# Twintig-FCC-Metacarpal.net
KiCad netlist of a schematic drawn in Altium Designer
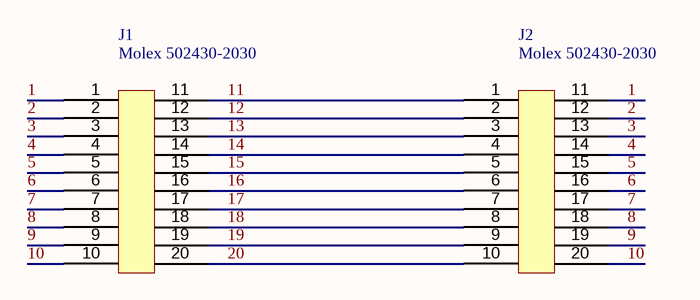
[diagram p0: Twintig-FCC-Metacarpal.SchDoc]

(export (version "E")
  (design (tool "Eeschema 10.0.6"))
  (components
    (comp (ref "J1")
      (value "Molex 502430-2030")
      (footprint "Molex 502430-2030")
      (libsource (lib "x-io") (part "Molex 502430-2030"))
    )
    (comp (ref "J2")
      (value "Molex 502430-2030")
      (footprint "Molex 502430-2030")
      (libsource (lib "x-io") (part "Molex 502430-2030"))
    )
  )
  (nets
    (net (code "1") (name "/1") (class "Default")
      (node (ref "J1") (pin "1") (pinfunction "1_1") (pintype "passive"))
      (node (ref "J2") (pin "11") (pinfunction "11_11") (pintype "passive"))
    )
    (net (code "2") (name "/2") (class "Default")
      (node (ref "J1") (pin "2") (pinfunction "2_2") (pintype "passive"))
      (node (ref "J2") (pin "12") (pinfunction "12_12") (pintype "passive"))
    )
    (net (code "3") (name "/3") (class "Default")
      (node (ref "J1") (pin "3") (pinfunction "3_3") (pintype "passive"))
      (node (ref "J2") (pin "13") (pinfunction "13_13") (pintype "passive"))
    )
    (net (code "4") (name "/4") (class "Default")
      (node (ref "J1") (pin "4") (pinfunction "4_4") (pintype "passive"))
      (node (ref "J2") (pin "14") (pinfunction "14_14") (pintype "passive"))
    )
    (net (code "5") (name "/5") (class "Default")
      (node (ref "J1") (pin "5") (pinfunction "5_5") (pintype "passive"))
      (node (ref "J2") (pin "15") (pinfunction "15_15") (pintype "passive"))
    )
    (net (code "6") (name "/6") (class "Default")
      (node (ref "J1") (pin "6") (pinfunction "6_6") (pintype "passive"))
      (node (ref "J2") (pin "16") (pinfunction "16_16") (pintype "passive"))
    )
    (net (code "7") (name "/7") (class "Default")
      (node (ref "J1") (pin "7") (pinfunction "7_7") (pintype "passive"))
      (node (ref "J2") (pin "17") (pinfunction "17_17") (pintype "passive"))
    )
    (net (code "8") (name "/8") (class "Default")
      (node (ref "J1") (pin "8") (pinfunction "8_8") (pintype "passive"))
      (node (ref "J2") (pin "18") (pinfunction "18_18") (pintype "passive"))
    )
    (net (code "9") (name "/9") (class "Default")
      (node (ref "J1") (pin "9") (pinfunction "9_9") (pintype "passive"))
      (node (ref "J2") (pin "19") (pinfunction "19_19") (pintype "passive"))
    )
    (net (code "10") (name "/10") (class "Default")
      (node (ref "J1") (pin "10") (pinfunction "10_10") (pintype "passive"))
      (node (ref "J2") (pin "20") (pinfunction "20_20") (pintype "passive"))
    )
    (net (code "11") (name "/11") (class "Default")
      (node (ref "J1") (pin "11") (pinfunction "11_11") (pintype "passive"))
      (node (ref "J2") (pin "1") (pinfunction "1_1") (pintype "passive"))
    )
    (net (code "12") (name "/12") (class "Default")
      (node (ref "J1") (pin "12") (pinfunction "12_12") (pintype "passive"))
      (node (ref "J2") (pin "2") (pinfunction "2_2") (pintype "passive"))
    )
    (net (code "13") (name "/13") (class "Default")
      (node (ref "J1") (pin "13") (pinfunction "13_13") (pintype "passive"))
      (node (ref "J2") (pin "3") (pinfunction "3_3") (pintype "passive"))
    )
    (net (code "14") (name "/14") (class "Default")
      (node (ref "J1") (pin "14") (pinfunction "14_14") (pintype "passive"))
      (node (ref "J2") (pin "4") (pinfunction "4_4") (pintype "passive"))
    )
    (net (code "15") (name "/15") (class "Default")
      (node (ref "J1") (pin "15") (pinfunction "15_15") (pintype "passive"))
      (node (ref "J2") (pin "5") (pinfunction "5_5") (pintype "passive"))
    )
    (net (code "16") (name "/16") (class "Default")
      (node (ref "J1") (pin "16") (pinfunction "16_16") (pintype "passive"))
      (node (ref "J2") (pin "6") (pinfunction "6_6") (pintype "passive"))
    )
    (net (code "17") (name "/17") (class "Default")
      (node (ref "J1") (pin "17") (pinfunction "17_17") (pintype "passive"))
      (node (ref "J2") (pin "7") (pinfunction "7_7") (pintype "passive"))
    )
    (net (code "18") (name "/18") (class "Default")
      (node (ref "J1") (pin "18") (pinfunction "18_18") (pintype "passive"))
      (node (ref "J2") (pin "8") (pinfunction "8_8") (pintype "passive"))
    )
    (net (code "19") (name "/19") (class "Default")
      (node (ref "J1") (pin "19") (pinfunction "19_19") (pintype "passive"))
      (node (ref "J2") (pin "9") (pinfunction "9_9") (pintype "passive"))
    )
    (net (code "20") (name "/20") (class "Default")
      (node (ref "J1") (pin "20") (pinfunction "20_20") (pintype "passive"))
      (node (ref "J2") (pin "10") (pinfunction "10_10") (pintype "passive"))
    )
  )
)
